# MEM.net
KiCad netlist of a schematic drawn in Altium Designer
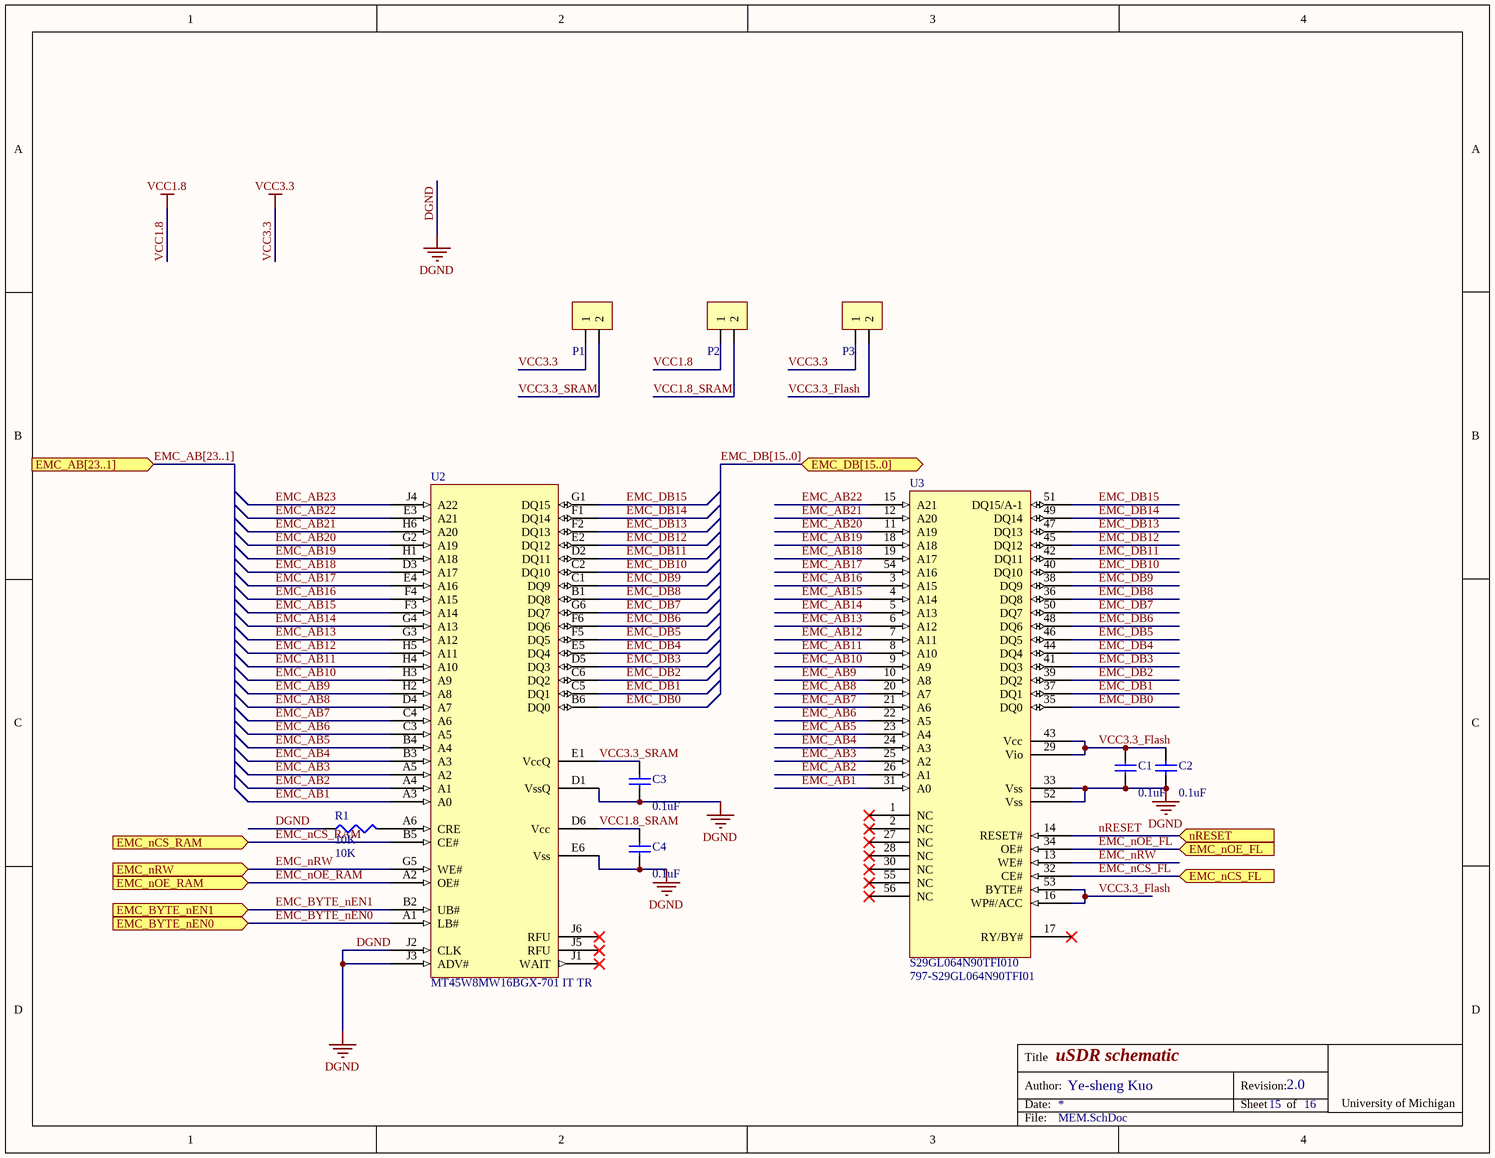
[diagram p0: MEM.SchDoc]

(export (version "E")
  (design (tool "Eeschema 10.0.6"))
  (components
    (comp (ref "C1")
      (value "0.1uF")
      (footprint "0402")
      (description "Capacitor (Semiconductor SIM Model)")
      (fields (field (name "PUBLISHER") "Altium Limited"))
      (libsource (lib "Miscellaneous Devices") (part "Cap Semi"))
    )
    (comp (ref "C2")
      (value "0.1uF")
      (footprint "0402")
      (description "Capacitor (Semiconductor SIM Model)")
      (fields (field (name "PUBLISHER") "Altium Limited"))
      (libsource (lib "Miscellaneous Devices") (part "Cap Semi"))
    )
    (comp (ref "C3")
      (value "0.1uF")
      (footprint "0402")
      (description "Capacitor (Semiconductor SIM Model)")
      (fields (field (name "PUBLISHER") "Altium Limited"))
      (libsource (lib "Miscellaneous Devices") (part "Cap Semi"))
    )
    (comp (ref "C4")
      (value "0.1uF")
      (footprint "0402")
      (description "Capacitor (Semiconductor SIM Model)")
      (fields (field (name "PUBLISHER") "Altium Limited"))
      (libsource (lib "Miscellaneous Devices") (part "Cap Semi"))
    )
    (comp (ref "P1")
      (value "1 x 2 header")
      (footprint "1x2 header")
      (description "100 mils standard header")
      (libsource (lib "SDR") (part "1 x 2 header"))
    )
    (comp (ref "P2")
      (value "1 x 2 header")
      (footprint "1x2 header")
      (description "100 mils standard header")
      (libsource (lib "SDR") (part "1 x 2 header"))
    )
    (comp (ref "P3")
      (value "1 x 2 header")
      (footprint "1x2 header")
      (description "100 mils standard header")
      (libsource (lib "SDR") (part "1 x 2 header"))
    )
    (comp (ref "R1")
      (value "10K")
      (footprint "0402")
      (description "Resistor")
      (fields (field (name "ALTIUM_VALUE") "10K") (field (name "PUBLISHER") "Altium Limited"))
      (libsource (lib "Miscellaneous Devices") (part "Res3"))
    )
    (comp (ref "U2")
      (value "MT45W8MW16BGX-701 IT TR")
      (footprint "BGA54C75P9X6_1000X800X70")
      (description "IC PSRAM 128MBIT 70NS 54VFBGA")
      (libsource (lib "SDR") (part "MT45W8MW16BGX-701 IT"))
    )
    (comp (ref "U3")
      (value "S29GL064N90TFI010")
      (footprint "TSSOP50P2000X120-56N")
      (description "Flash 3V 64Mb Float Gate highest address 90s")
      (fields (field (name "SUPPLIER PART NUMBER 1") "797-S29GL064N90TFI01"))
      (libsource (lib "SDR") (part "S29GL064N"))
    )
  )
  (nets
    (net (code "1") (name "/EMC_AB1") (class "Default")
      (node (ref "U2") (pin "A3") (pinfunction "A0_A3") (pintype "input"))
      (node (ref "U3") (pin "31") (pinfunction "A0_31") (pintype "input"))
    )
    (net (code "2") (name "/EMC_AB2") (class "Default")
      (node (ref "U2") (pin "A4") (pinfunction "A1_A4") (pintype "input"))
      (node (ref "U3") (pin "26") (pinfunction "A1_26") (pintype "input"))
    )
    (net (code "3") (name "/EMC_AB3") (class "Default")
      (node (ref "U2") (pin "A5") (pinfunction "A2_A5") (pintype "input"))
      (node (ref "U3") (pin "25") (pinfunction "A2_25") (pintype "input"))
    )
    (net (code "4") (name "/EMC_AB4") (class "Default")
      (node (ref "U2") (pin "B3") (pinfunction "A3_B3") (pintype "input"))
      (node (ref "U3") (pin "24") (pinfunction "A3_24") (pintype "input"))
    )
    (net (code "5") (name "/EMC_AB5") (class "Default")
      (node (ref "U2") (pin "B4") (pinfunction "A4_B4") (pintype "input"))
      (node (ref "U3") (pin "23") (pinfunction "A4_23") (pintype "input"))
    )
    (net (code "6") (name "/EMC_AB6") (class "Default")
      (node (ref "U2") (pin "C3") (pinfunction "A5_C3") (pintype "input"))
      (node (ref "U3") (pin "22") (pinfunction "A5_22") (pintype "input"))
    )
    (net (code "7") (name "/EMC_AB7") (class "Default")
      (node (ref "U2") (pin "C4") (pinfunction "A6_C4") (pintype "input"))
      (node (ref "U3") (pin "21") (pinfunction "A6_21") (pintype "input"))
    )
    (net (code "8") (name "/EMC_AB8") (class "Default")
      (node (ref "U2") (pin "D4") (pinfunction "A7_D4") (pintype "input"))
      (node (ref "U3") (pin "20") (pinfunction "A7_20") (pintype "input"))
    )
    (net (code "9") (name "/EMC_AB9") (class "Default")
      (node (ref "U2") (pin "H2") (pinfunction "A8_H2") (pintype "input"))
      (node (ref "U3") (pin "10") (pinfunction "A8_10") (pintype "input"))
    )
    (net (code "10") (name "/EMC_AB10") (class "Default")
      (node (ref "U2") (pin "H3") (pinfunction "A9_H3") (pintype "input"))
      (node (ref "U3") (pin "9") (pinfunction "A9_9") (pintype "input"))
    )
    (net (code "11") (name "/EMC_AB11") (class "Default")
      (node (ref "U2") (pin "H4") (pinfunction "A10_H4") (pintype "input"))
      (node (ref "U3") (pin "8") (pinfunction "A10_8") (pintype "input"))
    )
    (net (code "12") (name "/EMC_AB12") (class "Default")
      (node (ref "U2") (pin "H5") (pinfunction "A11_H5") (pintype "input"))
      (node (ref "U3") (pin "7") (pinfunction "A11_7") (pintype "input"))
    )
    (net (code "13") (name "/EMC_AB13") (class "Default")
      (node (ref "U2") (pin "G3") (pinfunction "A12_G3") (pintype "input"))
      (node (ref "U3") (pin "6") (pinfunction "A12_6") (pintype "input"))
    )
    (net (code "14") (name "/EMC_AB14") (class "Default")
      (node (ref "U2") (pin "G4") (pinfunction "A13_G4") (pintype "input"))
      (node (ref "U3") (pin "5") (pinfunction "A13_5") (pintype "input"))
    )
    (net (code "15") (name "/EMC_AB15") (class "Default")
      (node (ref "U2") (pin "F3") (pinfunction "A14_F3") (pintype "input"))
      (node (ref "U3") (pin "4") (pinfunction "A14_4") (pintype "input"))
    )
    (net (code "16") (name "/EMC_AB16") (class "Default")
      (node (ref "U2") (pin "F4") (pinfunction "A15_F4") (pintype "input"))
      (node (ref "U3") (pin "3") (pinfunction "A15_3") (pintype "input"))
    )
    (net (code "17") (name "/EMC_AB17") (class "Default")
      (node (ref "U2") (pin "E4") (pinfunction "A16_E4") (pintype "input"))
      (node (ref "U3") (pin "54") (pinfunction "A16_54") (pintype "input"))
    )
    (net (code "18") (name "/EMC_AB18") (class "Default")
      (node (ref "U2") (pin "D3") (pinfunction "A17_D3") (pintype "input"))
      (node (ref "U3") (pin "19") (pinfunction "A17_19") (pintype "input"))
    )
    (net (code "19") (name "/EMC_AB19") (class "Default")
      (node (ref "U2") (pin "H1") (pinfunction "A18_H1") (pintype "input"))
      (node (ref "U3") (pin "18") (pinfunction "A18_18") (pintype "input"))
    )
    (net (code "20") (name "/EMC_AB20") (class "Default")
      (node (ref "U2") (pin "G2") (pinfunction "A19_G2") (pintype "input"))
      (node (ref "U3") (pin "11") (pinfunction "A19_11") (pintype "input"))
    )
    (net (code "21") (name "/EMC_AB21") (class "Default")
      (node (ref "U2") (pin "H6") (pinfunction "A20_H6") (pintype "input"))
      (node (ref "U3") (pin "12") (pinfunction "A20_12") (pintype "input"))
    )
    (net (code "22") (name "/EMC_AB22") (class "Default")
      (node (ref "U2") (pin "E3") (pinfunction "A21_E3") (pintype "input"))
      (node (ref "U3") (pin "15") (pinfunction "A21_15") (pintype "input"))
    )
    (net (code "23") (name "/EMC_AB23") (class "Default")
      (node (ref "U2") (pin "J4") (pinfunction "A22_J4") (pintype "input"))
    )
    (net (code "25") (name "/EMC_BYTE_nEN0") (class "Default")
      (node (ref "U2") (pin "A1") (pinfunction "LB#_A1") (pintype "input"))
    )
    (net (code "26") (name "/EMC_BYTE_nEN1") (class "Default")
      (node (ref "U2") (pin "B2") (pinfunction "UB#_B2") (pintype "input"))
    )
    (net (code "27") (name "/EMC_DB0") (class "Default")
      (node (ref "U2") (pin "B6") (pinfunction "DQ0_B6") (pintype "bidirectional"))
      (node (ref "U3") (pin "35") (pinfunction "DQ0_35") (pintype "bidirectional"))
    )
    (net (code "28") (name "/EMC_DB1") (class "Default")
      (node (ref "U2") (pin "C5") (pinfunction "DQ1_C5") (pintype "bidirectional"))
      (node (ref "U3") (pin "37") (pinfunction "DQ1_37") (pintype "bidirectional"))
    )
    (net (code "29") (name "/EMC_DB2") (class "Default")
      (node (ref "U2") (pin "C6") (pinfunction "DQ2_C6") (pintype "bidirectional"))
      (node (ref "U3") (pin "39") (pinfunction "DQ2_39") (pintype "bidirectional"))
    )
    (net (code "30") (name "/EMC_DB3") (class "Default")
      (node (ref "U2") (pin "D5") (pinfunction "DQ3_D5") (pintype "bidirectional"))
      (node (ref "U3") (pin "41") (pinfunction "DQ3_41") (pintype "bidirectional"))
    )
    (net (code "31") (name "/EMC_DB4") (class "Default")
      (node (ref "U2") (pin "E5") (pinfunction "DQ4_E5") (pintype "bidirectional"))
      (node (ref "U3") (pin "44") (pinfunction "DQ4_44") (pintype "bidirectional"))
    )
    (net (code "32") (name "/EMC_DB5") (class "Default")
      (node (ref "U2") (pin "F5") (pinfunction "DQ5_F5") (pintype "bidirectional"))
      (node (ref "U3") (pin "46") (pinfunction "DQ5_46") (pintype "bidirectional"))
    )
    (net (code "33") (name "/EMC_DB6") (class "Default")
      (node (ref "U2") (pin "F6") (pinfunction "DQ6_F6") (pintype "bidirectional"))
      (node (ref "U3") (pin "48") (pinfunction "DQ6_48") (pintype "bidirectional"))
    )
    (net (code "34") (name "/EMC_DB7") (class "Default")
      (node (ref "U2") (pin "G6") (pinfunction "DQ7_G6") (pintype "bidirectional"))
      (node (ref "U3") (pin "50") (pinfunction "DQ7_50") (pintype "bidirectional"))
    )
    (net (code "35") (name "/EMC_DB8") (class "Default")
      (node (ref "U2") (pin "B1") (pinfunction "DQ8_B1") (pintype "bidirectional"))
      (node (ref "U3") (pin "36") (pinfunction "DQ8_36") (pintype "bidirectional"))
    )
    (net (code "36") (name "/EMC_DB9") (class "Default")
      (node (ref "U2") (pin "C1") (pinfunction "DQ9_C1") (pintype "bidirectional"))
      (node (ref "U3") (pin "38") (pinfunction "DQ9_38") (pintype "bidirectional"))
    )
    (net (code "37") (name "/EMC_DB10") (class "Default")
      (node (ref "U2") (pin "C2") (pinfunction "DQ10_C2") (pintype "bidirectional"))
      (node (ref "U3") (pin "40") (pinfunction "DQ10_40") (pintype "bidirectional"))
    )
    (net (code "38") (name "/EMC_DB11") (class "Default")
      (node (ref "U2") (pin "D2") (pinfunction "DQ11_D2") (pintype "bidirectional"))
      (node (ref "U3") (pin "42") (pinfunction "DQ11_42") (pintype "bidirectional"))
    )
    (net (code "39") (name "/EMC_DB12") (class "Default")
      (node (ref "U2") (pin "E2") (pinfunction "DQ12_E2") (pintype "bidirectional"))
      (node (ref "U3") (pin "45") (pinfunction "DQ12_45") (pintype "bidirectional"))
    )
    (net (code "40") (name "/EMC_DB13") (class "Default")
      (node (ref "U2") (pin "F2") (pinfunction "DQ13_F2") (pintype "bidirectional"))
      (node (ref "U3") (pin "47") (pinfunction "DQ13_47") (pintype "bidirectional"))
    )
    (net (code "41") (name "/EMC_DB14") (class "Default")
      (node (ref "U2") (pin "F1") (pinfunction "DQ14_F1") (pintype "bidirectional"))
      (node (ref "U3") (pin "49") (pinfunction "DQ14_49") (pintype "bidirectional"))
    )
    (net (code "42") (name "/EMC_DB15") (class "Default")
      (node (ref "U2") (pin "G1") (pinfunction "DQ15_G1") (pintype "bidirectional"))
      (node (ref "U3") (pin "51") (pinfunction "DQ15/A-1_51") (pintype "bidirectional"))
    )
    (net (code "44") (name "/EMC_nCS_FL") (class "Default")
      (node (ref "U3") (pin "32") (pinfunction "CE#_32") (pintype "input"))
    )
    (net (code "45") (name "/EMC_nCS_RAM") (class "Default")
      (node (ref "U2") (pin "B5") (pinfunction "CE#_B5") (pintype "input"))
    )
    (net (code "46") (name "/EMC_nOE_FL") (class "Default")
      (node (ref "U3") (pin "34") (pinfunction "OE#_34") (pintype "input"))
    )
    (net (code "47") (name "/EMC_nOE_RAM") (class "Default")
      (node (ref "U2") (pin "A2") (pinfunction "OE#_A2") (pintype "input"))
    )
    (net (code "48") (name "/EMC_nRW") (class "Default")
      (node (ref "U2") (pin "G5") (pinfunction "WE#_G5") (pintype "input"))
      (node (ref "U3") (pin "13") (pinfunction "WE#_13") (pintype "input"))
    )
    (net (code "49") (name "/VCC1.8_SRAM") (class "Default")
      (node (ref "C4") (pin "2") (pinfunction "2_2") (pintype "passive"))
      (node (ref "P2") (pin "2") (pinfunction "2_2") (pintype "passive"))
      (node (ref "U2") (pin "D6") (pinfunction "Vcc_D6") (pintype "power_in"))
    )
    (net (code "50") (name "/VCC3.3_Flash") (class "Default")
      (node (ref "C1") (pin "2") (pinfunction "2_2") (pintype "passive"))
      (node (ref "C2") (pin "2") (pinfunction "2_2") (pintype "passive"))
      (node (ref "P3") (pin "2") (pinfunction "2_2") (pintype "passive"))
      (node (ref "U3") (pin "16") (pinfunction "WP#/ACC_16") (pintype "input"))
      (node (ref "U3") (pin "29") (pinfunction "Vio_29") (pintype "power_in"))
      (node (ref "U3") (pin "43") (pinfunction "Vcc_43") (pintype "power_in"))
      (node (ref "U3") (pin "53") (pinfunction "BYTE#_53") (pintype "input"))
    )
    (net (code "51") (name "/VCC3.3_SRAM") (class "Default")
      (node (ref "C3") (pin "2") (pinfunction "2_2") (pintype "passive"))
      (node (ref "P1") (pin "2") (pinfunction "2_2") (pintype "passive"))
      (node (ref "U2") (pin "E1") (pinfunction "VccQ_E1") (pintype "power_in"))
    )
    (net (code "52") (name "/nRESET") (class "Default")
      (node (ref "U3") (pin "14") (pinfunction "RESET#_14") (pintype "input"))
    )
    (net (code "53") (name "DGND") (class "Default")
      (node (ref "C1") (pin "1") (pinfunction "1_1") (pintype "passive"))
      (node (ref "C2") (pin "1") (pinfunction "1_1") (pintype "passive"))
      (node (ref "C3") (pin "1") (pinfunction "1_1") (pintype "passive"))
      (node (ref "C4") (pin "1") (pinfunction "1_1") (pintype "passive"))
      (node (ref "R1") (pin "1") (pinfunction "1_1") (pintype "passive"))
      (node (ref "U2") (pin "D1") (pinfunction "VssQ_D1") (pintype "power_in"))
      (node (ref "U2") (pin "E6") (pinfunction "Vss_E6") (pintype "power_in"))
      (node (ref "U2") (pin "J2") (pinfunction "CLK_J2") (pintype "input"))
      (node (ref "U2") (pin "J3") (pinfunction "ADV#_J3") (pintype "input"))
      (node (ref "U3") (pin "33") (pinfunction "Vss_33") (pintype "power_in"))
      (node (ref "U3") (pin "52") (pinfunction "Vss_52") (pintype "power_in"))
    )
    (net (code "54") (name "Net-(U2-CRE)") (class "Default")
      (node (ref "R1") (pin "2") (pinfunction "2_2") (pintype "passive"))
      (node (ref "U2") (pin "A6") (pinfunction "CRE_A6") (pintype "input"))
    )
    (net (code "55") (name "VCC1.8") (class "Default")
      (node (ref "P2") (pin "1") (pinfunction "1_1") (pintype "passive"))
    )
    (net (code "56") (name "VCC3.3") (class "Default")
      (node (ref "P1") (pin "1") (pinfunction "1_1") (pintype "passive"))
      (node (ref "P3") (pin "1") (pinfunction "1_1") (pintype "passive"))
    )
    (net (code "57") (name "unconnected-(U2-RFU-PadJ5)") (class "Default")
      (node (ref "U2") (pin "J5") (pinfunction "RFU_J5") (pintype "passive+no_connect"))
    )
    (net (code "58") (name "unconnected-(U2-RFU-PadJ6)") (class "Default")
      (node (ref "U2") (pin "J6") (pinfunction "RFU_J6") (pintype "passive+no_connect"))
    )
    (net (code "59") (name "unconnected-(U2-WAIT-PadJ1)") (class "Default")
      (node (ref "U2") (pin "J1") (pinfunction "WAIT_J1") (pintype "output+no_connect"))
    )
    (net (code "60") (name "unconnected-(U3-NC-Pad1)") (class "Default")
      (node (ref "U3") (pin "1") (pinfunction "NC_1") (pintype "passive+no_connect"))
    )
    (net (code "61") (name "unconnected-(U3-NC-Pad2)") (class "Default")
      (node (ref "U3") (pin "2") (pinfunction "NC_2") (pintype "passive+no_connect"))
    )
    (net (code "62") (name "unconnected-(U3-NC-Pad27)") (class "Default")
      (node (ref "U3") (pin "27") (pinfunction "NC_27") (pintype "passive+no_connect"))
    )
    (net (code "63") (name "unconnected-(U3-NC-Pad28)") (class "Default")
      (node (ref "U3") (pin "28") (pinfunction "NC_28") (pintype "passive+no_connect"))
    )
    (net (code "64") (name "unconnected-(U3-NC-Pad30)") (class "Default")
      (node (ref "U3") (pin "30") (pinfunction "NC_30") (pintype "passive+no_connect"))
    )
    (net (code "65") (name "unconnected-(U3-NC-Pad55)") (class "Default")
      (node (ref "U3") (pin "55") (pinfunction "NC_55") (pintype "passive+no_connect"))
    )
    (net (code "66") (name "unconnected-(U3-NC-Pad56)") (class "Default")
      (node (ref "U3") (pin "56") (pinfunction "NC_56") (pintype "passive+no_connect"))
    )
    (net (code "67") (name "unconnected-(U3-RY{slash}BY#-Pad17)") (class "Default")
      (node (ref "U3") (pin "17") (pinfunction "RY/BY#_17") (pintype "passive+no_connect"))
    )
  )
)
